# STM32L010F4P6.net
KiCad netlist of a schematic drawn in EAGLE
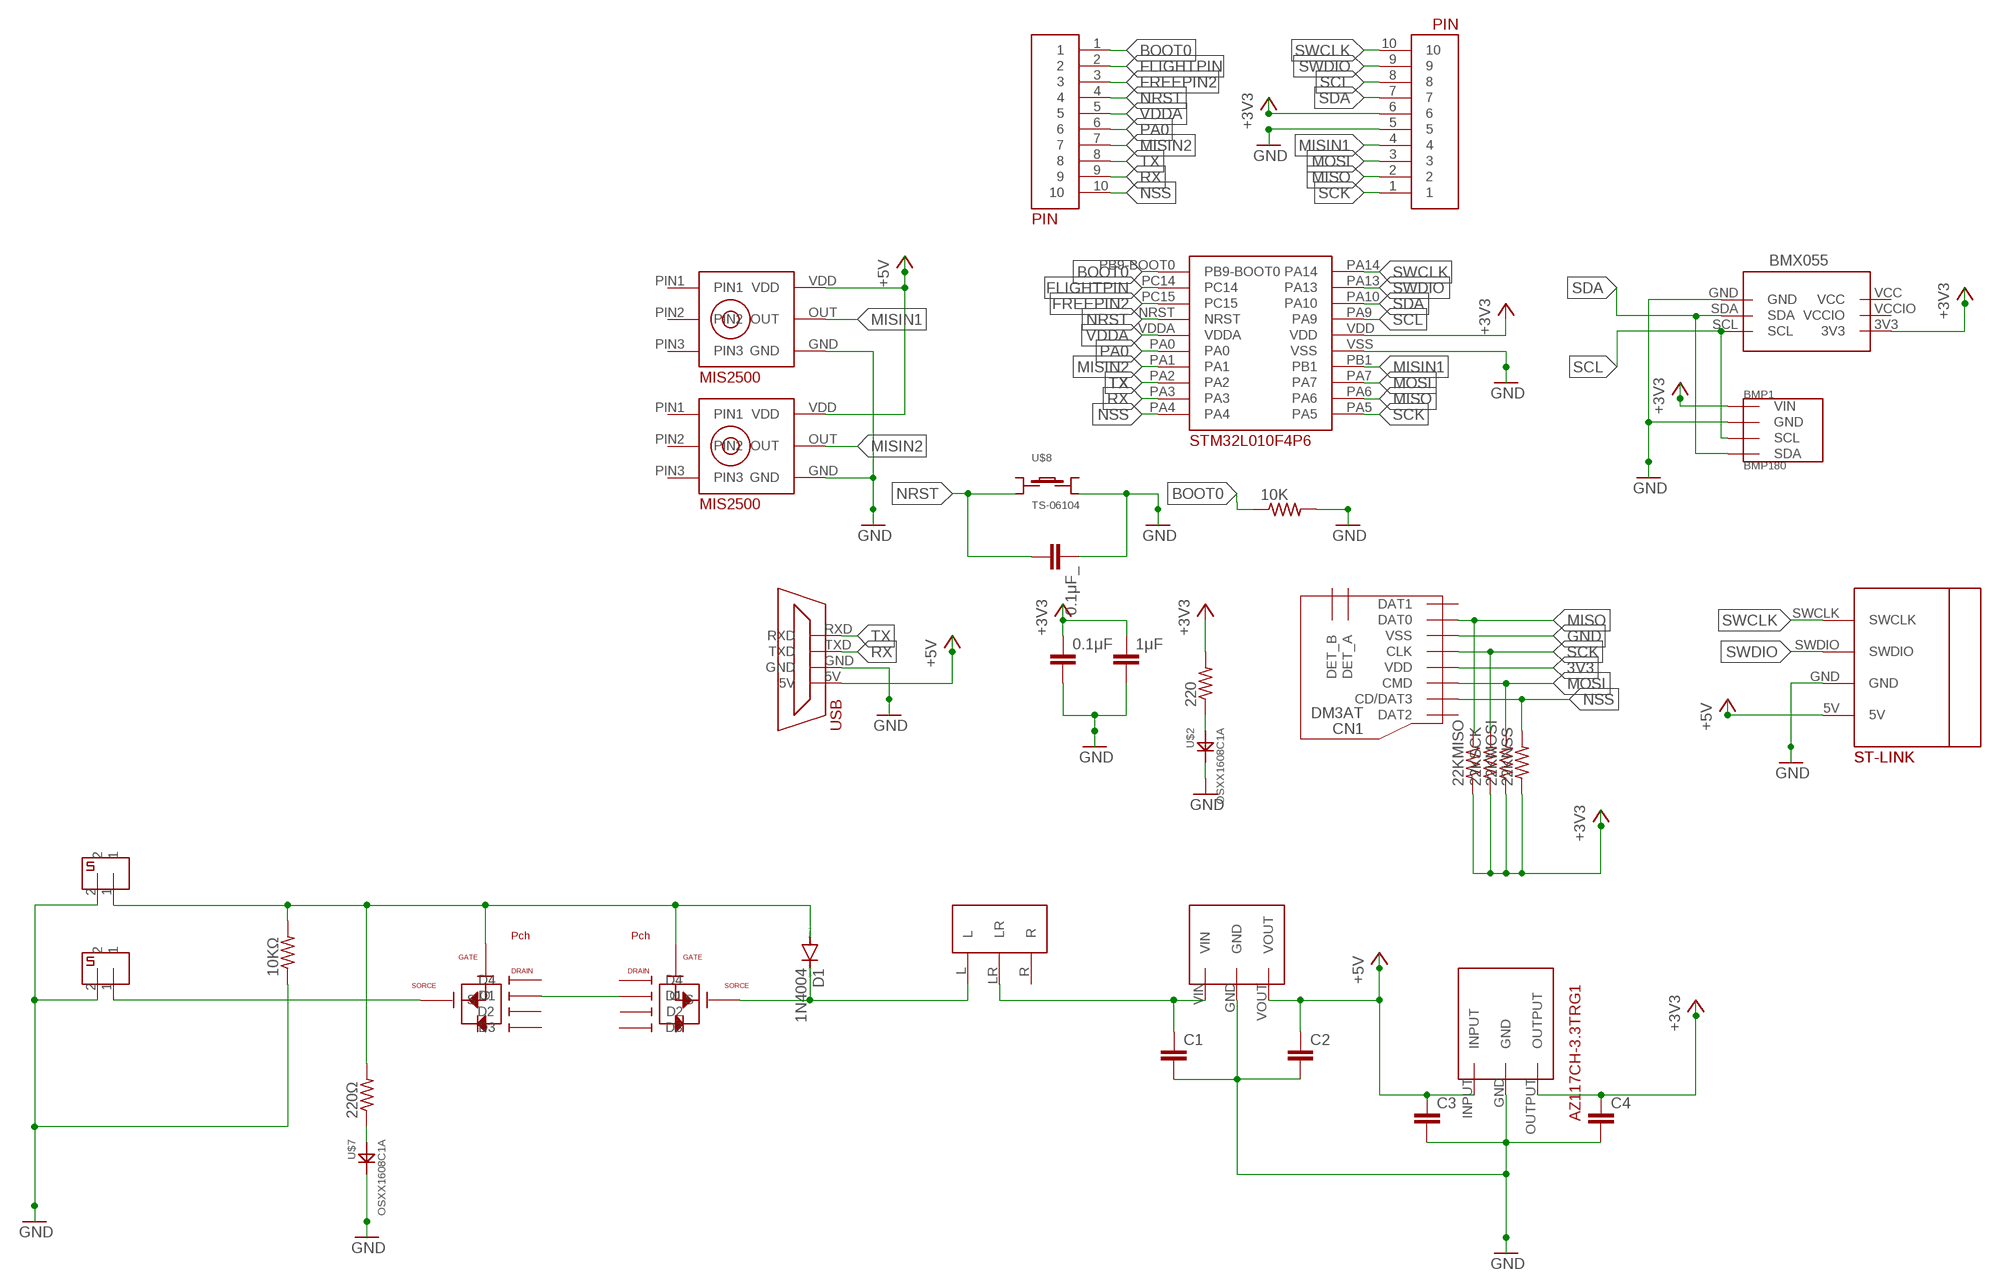
[diagram p0: schematic, sheet 1]

(export (version "E")
  (design (tool "Eeschema 10.0.6"))
  (components
    (comp (ref "0.1μF")
      (value "C-EUC0603")
      (footprint "eagle-import:C0603")
      (libsource (lib "eagle-import") (part "C-EUC0603"))
    )
    (comp (ref "0.1μF_")
      (value "C-EUC0603")
      (footprint "eagle-import:C0603")
      (libsource (lib "eagle-import") (part "C-EUC0603"))
    )
    (comp (ref "1μF")
      (value "C-EUC0805")
      (footprint "eagle-import:C0805")
      (libsource (lib "eagle-import") (part "C-EUC0805"))
    )
    (comp (ref "10K")
      (value "R-US_R0603")
      (footprint "eagle-import:R0603")
      (libsource (lib "eagle-import") (part "R-US_R0603"))
    )
    (comp (ref "10KΩ")
      (value "R-US_R0603")
      (footprint "eagle-import:R0603")
      (libsource (lib "eagle-import") (part "R-US_R0603"))
    )
    (comp (ref "22KMISO")
      (value "R-US_R0603")
      (footprint "eagle-import:R0603")
      (libsource (lib "eagle-import") (part "R-US_R0603"))
    )
    (comp (ref "22KMOSI")
      (value "R-US_R0603")
      (footprint "eagle-import:R0603")
      (libsource (lib "eagle-import") (part "R-US_R0603"))
    )
    (comp (ref "22KNSS")
      (value "R-US_R0603")
      (footprint "eagle-import:R0603")
      (libsource (lib "eagle-import") (part "R-US_R0603"))
    )
    (comp (ref "22KSCK")
      (value "R-US_R0603")
      (footprint "eagle-import:R0603")
      (libsource (lib "eagle-import") (part "R-US_R0603"))
    )
    (comp (ref "220")
      (value "R-US_R0603")
      (footprint "eagle-import:R0603")
      (libsource (lib "eagle-import") (part "R-US_R0603"))
    )
    (comp (ref "220Ω")
      (value "R-US_R0603")
      (footprint "eagle-import:R0603")
      (libsource (lib "eagle-import") (part "R-US_R0603"))
    )
    (comp (ref "BMP1")
      (value "BMP180")
      (footprint "eagle-import:GY-68")
      (libsource (lib "eagle-import") (part "BMP180"))
    )
    (comp (ref "BMX1")
      (value "BMX055")
      (footprint "eagle-import:BMX055")
      (libsource (lib "eagle-import") (part "BMX055"))
    )
    (comp (ref "C1")
      (value "C2,5-3")
      (footprint "eagle-import:C2.5-3")
      (libsource (lib "eagle-import") (part "C2,5-3"))
    )
    (comp (ref "C2")
      (value "C2,5-3")
      (footprint "eagle-import:C2.5-3")
      (libsource (lib "eagle-import") (part "C2,5-3"))
    )
    (comp (ref "C3")
      (value "C2,5-3")
      (footprint "eagle-import:C2.5-3")
      (libsource (lib "eagle-import") (part "C2,5-3"))
    )
    (comp (ref "C4")
      (value "C2,5-3")
      (footprint "eagle-import:C2.5-3")
      (libsource (lib "eagle-import") (part "C2,5-3"))
    )
    (comp (ref "CN1")
      (value "DM3AT")
      (footprint "eagle-import:DM3AT")
      (libsource (lib "eagle-import") (part "DM3AT"))
    )
    (comp (ref "CONNECTOR1")
      (value "2PIN")
      (footprint "eagle-import:2PIN")
      (libsource (lib "eagle-import") (part "2PIN"))
    )
    (comp (ref "CONNECTOR3")
      (value "2PIN")
      (footprint "eagle-import:2PIN")
      (libsource (lib "eagle-import") (part "2PIN"))
    )
    (comp (ref "D1")
      (value "1N4004")
      (footprint "eagle-import:DO41-10")
      (libsource (lib "eagle-import") (part "1N4004"))
    )
    (comp (ref "SRIDE_SWTCH1")
      (value "SRIDE_SWITCH")
      (footprint "eagle-import:SRIDE_SWITCH")
      (libsource (lib "eagle-import") (part "SRIDE_SWITCH"))
    )
    (comp (ref "U$1")
      (value "STM32L010F4P6")
      (footprint "eagle-import:STM32L010F4P6")
      (libsource (lib "eagle-import") (part "STM32L010F4P6"))
    )
    (comp (ref "U$2")
      (value "OSXX1608C1A")
      (footprint "eagle-import:OSXX1608C1A")
      (libsource (lib "eagle-import") (part "OSXX1608C1A"))
    )
    (comp (ref "U$3")
      (value "MIS2500")
      (footprint "eagle-import:MIS2500")
      (libsource (lib "eagle-import") (part "MIS2500"))
    )
    (comp (ref "U$4")
      (value "MIS2500")
      (footprint "eagle-import:MIS2500")
      (libsource (lib "eagle-import") (part "MIS2500"))
    )
    (comp (ref "U$5")
      (value "STLINK")
      (footprint "eagle-import:STLINK")
      (libsource (lib "eagle-import") (part "STLINK"))
    )
    (comp (ref "U$6")
      (value "SSM6J808R")
      (footprint "eagle-import:SSM6J808R")
      (libsource (lib "eagle-import") (part "SSM6J808R"))
    )
    (comp (ref "U$7")
      (value "OSXX1608C1A")
      (footprint "eagle-import:OSXX1608C1A")
      (libsource (lib "eagle-import") (part "OSXX1608C1A"))
    )
    (comp (ref "U$8")
      (value "TS-06104")
      (footprint "eagle-import:TS-06104")
      (libsource (lib "eagle-import") (part "TS-06104"))
    )
    (comp (ref "U$9")
      (value "SSM6J808R")
      (footprint "eagle-import:SSM6J808R")
      (libsource (lib "eagle-import") (part "SSM6J808R"))
    )
    (comp (ref "U$11")
      (value "M78AR05-1")
      (footprint "eagle-import:M78AR05-1")
      (libsource (lib "eagle-import") (part "M78AR05-1"))
    )
    (comp (ref "U$12")
      (value "10PIN")
      (footprint "eagle-import:10PIN")
      (libsource (lib "eagle-import") (part "10PIN"))
    )
    (comp (ref "U$13")
      (value "10PIN")
      (footprint "eagle-import:10PIN")
      (libsource (lib "eagle-import") (part "10PIN"))
    )
    (comp (ref "U$14")
      (value "F234X")
      (footprint "eagle-import:FT234X")
      (libsource (lib "eagle-import") (part "F234X"))
    )
    (comp (ref "U$17")
      (value "AZ117CH-3.3TRG1")
      (footprint "eagle-import:AZ117CH-3.3TRG1")
      (libsource (lib "eagle-import") (part "AZ117CH-3.3TRG1"))
    )
  )
  (nets
    (net (code "1") (name "+3V3") (class "Default")
      (node (ref "0.1μF") (pin "1") (pinfunction "1_1") (pintype "passive"))
      (node (ref "1μF") (pin "1") (pinfunction "1_1") (pintype "passive"))
      (node (ref "220") (pin "2") (pinfunction "2_2") (pintype "passive"))
      (node (ref "22KMISO") (pin "1") (pinfunction "1_1") (pintype "passive"))
      (node (ref "22KMOSI") (pin "1") (pinfunction "1_1") (pintype "passive"))
      (node (ref "22KNSS") (pin "1") (pinfunction "1_1") (pintype "passive"))
      (node (ref "22KSCK") (pin "1") (pinfunction "1_1") (pintype "passive"))
      (node (ref "BMP1") (pin "P1") (pinfunction "VIN_P1") (pintype "bidirectional"))
      (node (ref "BMX1") (pin "3V3") (pinfunction "3V3_3V3") (pintype "power_in"))
      (node (ref "C4") (pin "1") (pinfunction "1_1") (pintype "passive"))
      (node (ref "U$1") (pin "VDD") (pinfunction "VDD_VDD") (pintype "power_in"))
      (node (ref "U$13") (pin "6") (pinfunction "6_6") (pintype "bidirectional"))
      (node (ref "U$17") (pin "OUTPUT") (pinfunction "OUTPUT_OUTPUT") (pintype "bidirectional"))
    )
    (net (code "2") (name "+5V") (class "Default")
      (node (ref "C2") (pin "1") (pinfunction "1_1") (pintype "passive"))
      (node (ref "C3") (pin "1") (pinfunction "1_1") (pintype "passive"))
      (node (ref "U$11") (pin "VOUT") (pinfunction "VOUT_VOUT") (pintype "bidirectional"))
      (node (ref "U$14") (pin "5V") (pinfunction "5V_5V") (pintype "bidirectional"))
      (node (ref "U$17") (pin "INPUT") (pinfunction "INPUT_INPUT") (pintype "bidirectional"))
      (node (ref "U$3") (pin "VDD") (pinfunction "VDD_VDD") (pintype "bidirectional"))
      (node (ref "U$4") (pin "VDD") (pinfunction "VDD_VDD") (pintype "bidirectional"))
      (node (ref "U$5") (pin "5V") (pinfunction "5V_5V") (pintype "bidirectional"))
    )
    (net (code "3") (name "/VCC") (class "Default")
      (node (ref "BMX1") (pin "VCC") (pinfunction "VCC_VCC") (pintype "power_in"))
    )
    (net (code "4") (name "/VCCIO") (class "Default")
      (node (ref "BMX1") (pin "VCCIO") (pinfunction "VCCIO_VCCIO") (pintype "power_in"))
    )
    (net (code "5") (name "3V3") (class "Default")
      (node (ref "CN1") (pin "VDD") (pinfunction "VDD_VDD") (pintype "bidirectional"))
    )
    (net (code "6") (name "BOOT0") (class "Default")
      (node (ref "10K") (pin "1") (pinfunction "1_1") (pintype "passive"))
      (node (ref "U$1") (pin "PB9-BOOT0") (pinfunction "PB9-BOOT0_PB9-BOOT0") (pintype "bidirectional"))
      (node (ref "U$12") (pin "1") (pinfunction "1_1") (pintype "bidirectional"))
    )
    (net (code "7") (name "FLIGHTPIN") (class "Default")
      (node (ref "U$1") (pin "PC14") (pinfunction "PC14_PC14") (pintype "bidirectional"))
      (node (ref "U$12") (pin "2") (pinfunction "2_2") (pintype "bidirectional"))
    )
    (net (code "8") (name "FREEPIN2") (class "Default")
      (node (ref "U$1") (pin "PC15") (pinfunction "PC15_PC15") (pintype "bidirectional"))
      (node (ref "U$12") (pin "3") (pinfunction "3_3") (pintype "bidirectional"))
    )
    (net (code "9") (name "GND") (class "Default")
      (node (ref "0.1μF") (pin "2") (pinfunction "2_2") (pintype "passive"))
      (node (ref "0.1μF_") (pin "1") (pinfunction "1_1") (pintype "passive"))
      (node (ref "10K") (pin "2") (pinfunction "2_2") (pintype "passive"))
      (node (ref "10KΩ") (pin "1") (pinfunction "1_1") (pintype "passive"))
      (node (ref "1μF") (pin "2") (pinfunction "2_2") (pintype "passive"))
      (node (ref "BMP1") (pin "P2") (pinfunction "GND_P2") (pintype "bidirectional"))
      (node (ref "BMX1") (pin "GND") (pinfunction "GND_GND") (pintype "power_in"))
      (node (ref "C1") (pin "2") (pinfunction "2_2") (pintype "passive"))
      (node (ref "C2") (pin "2") (pinfunction "2_2") (pintype "passive"))
      (node (ref "C3") (pin "2") (pinfunction "2_2") (pintype "passive"))
      (node (ref "C4") (pin "2") (pinfunction "2_2") (pintype "passive"))
      (node (ref "CN1") (pin "VSS") (pinfunction "VSS_VSS") (pintype "bidirectional"))
      (node (ref "CONNECTOR1") (pin "2") (pinfunction "2_2") (pintype "bidirectional"))
      (node (ref "CONNECTOR3") (pin "2") (pinfunction "2_2") (pintype "bidirectional"))
      (node (ref "U$1") (pin "VSS") (pinfunction "VSS_VSS") (pintype "power_in"))
      (node (ref "U$11") (pin "GND") (pinfunction "GND_GND") (pintype "bidirectional"))
      (node (ref "U$13") (pin "5") (pinfunction "5_5") (pintype "bidirectional"))
      (node (ref "U$14") (pin "GND") (pinfunction "GND_GND") (pintype "bidirectional"))
      (node (ref "U$17") (pin "GND") (pinfunction "GND_GND") (pintype "bidirectional"))
      (node (ref "U$2") (pin "CT") (pinfunction "CT_CT") (pintype "bidirectional"))
      (node (ref "U$3") (pin "GND") (pinfunction "GND_GND") (pintype "bidirectional"))
      (node (ref "U$4") (pin "GND") (pinfunction "GND_GND") (pintype "bidirectional"))
      (node (ref "U$5") (pin "GND") (pinfunction "GND_GND") (pintype "bidirectional"))
      (node (ref "U$7") (pin "CT") (pinfunction "CT_CT") (pintype "bidirectional"))
      (node (ref "U$8") (pin "D") (pinfunction "D_D") (pintype "bidirectional"))
    )
    (net (code "10") (name "MISIN1") (class "Default")
      (node (ref "U$1") (pin "PB1") (pinfunction "PB1_PB1") (pintype "bidirectional"))
      (node (ref "U$13") (pin "4") (pinfunction "4_4") (pintype "bidirectional"))
      (node (ref "U$3") (pin "OUT") (pinfunction "OUT_OUT") (pintype "bidirectional"))
    )
    (net (code "11") (name "MISIN2") (class "Default")
      (node (ref "U$1") (pin "PA1") (pinfunction "PA1_PA1") (pintype "bidirectional"))
      (node (ref "U$12") (pin "7") (pinfunction "7_7") (pintype "bidirectional"))
      (node (ref "U$4") (pin "OUT") (pinfunction "OUT_OUT") (pintype "bidirectional"))
    )
    (net (code "12") (name "MISO") (class "Default")
      (node (ref "22KMISO") (pin "2") (pinfunction "2_2") (pintype "passive"))
      (node (ref "CN1") (pin "DAT0") (pinfunction "DAT0_DAT0") (pintype "bidirectional"))
      (node (ref "U$1") (pin "PA6") (pinfunction "PA6_PA6") (pintype "bidirectional"))
      (node (ref "U$13") (pin "2") (pinfunction "2_2") (pintype "bidirectional"))
    )
    (net (code "13") (name "MOSI") (class "Default")
      (node (ref "22KMOSI") (pin "2") (pinfunction "2_2") (pintype "passive"))
      (node (ref "CN1") (pin "CMD") (pinfunction "CMD_CMD") (pintype "bidirectional"))
      (node (ref "U$1") (pin "PA7") (pinfunction "PA7_PA7") (pintype "bidirectional"))
      (node (ref "U$13") (pin "3") (pinfunction "3_3") (pintype "bidirectional"))
    )
    (net (code "14") (name "NRST") (class "Default")
      (node (ref "0.1μF_") (pin "2") (pinfunction "2_2") (pintype "passive"))
      (node (ref "U$1") (pin "NRST") (pinfunction "NRST_NRST") (pintype "bidirectional"))
      (node (ref "U$12") (pin "4") (pinfunction "4_4") (pintype "bidirectional"))
      (node (ref "U$8") (pin "B") (pinfunction "B_B") (pintype "bidirectional"))
    )
    (net (code "15") (name "NSS") (class "Default")
      (node (ref "22KNSS") (pin "2") (pinfunction "2_2") (pintype "passive"))
      (node (ref "CN1") (pin "CD/DAT3") (pinfunction "CD/DAT3_CD/DAT3") (pintype "bidirectional"))
      (node (ref "U$1") (pin "PA4") (pinfunction "PA4_PA4") (pintype "bidirectional"))
      (node (ref "U$12") (pin "10") (pinfunction "10_10") (pintype "bidirectional"))
    )
    (net (code "16") (name "Net-(10KΩ-Pad2)") (class "Default")
      (node (ref "10KΩ") (pin "2") (pinfunction "2_2") (pintype "passive"))
      (node (ref "220Ω") (pin "2") (pinfunction "2_2") (pintype "passive"))
      (node (ref "CONNECTOR1") (pin "1") (pinfunction "1_1") (pintype "bidirectional"))
      (node (ref "D1") (pin "A") (pinfunction "A_A") (pintype "passive"))
      (node (ref "U$6") (pin "G") (pinfunction "G_G") (pintype "bidirectional"))
      (node (ref "U$9") (pin "G") (pinfunction "G_G") (pintype "bidirectional"))
    )
    (net (code "17") (name "Net-(220-Pad1)") (class "Default")
      (node (ref "220") (pin "1") (pinfunction "1_1") (pintype "passive"))
      (node (ref "U$2") (pin "AN") (pinfunction "AN_AN") (pintype "bidirectional"))
    )
    (net (code "18") (name "Net-(220Ω-Pad1)") (class "Default")
      (node (ref "220Ω") (pin "1") (pinfunction "1_1") (pintype "passive"))
      (node (ref "U$7") (pin "AN") (pinfunction "AN_AN") (pintype "bidirectional"))
    )
    (net (code "19") (name "Net-(C1-Pad1)") (class "Default")
      (node (ref "C1") (pin "1") (pinfunction "1_1") (pintype "passive"))
      (node (ref "SRIDE_SWTCH1") (pin "LR") (pinfunction "LR_LR") (pintype "bidirectional"))
      (node (ref "U$11") (pin "VIN") (pinfunction "VIN_VIN") (pintype "bidirectional"))
    )
    (net (code "20") (name "Net-(CONNECTOR3-Pad1)") (class "Default")
      (node (ref "CONNECTOR3") (pin "1") (pinfunction "1_1") (pintype "bidirectional"))
      (node (ref "U$6") (pin "S") (pinfunction "S_S") (pintype "bidirectional"))
    )
    (net (code "21") (name "Net-(D1-PadC)") (class "Default")
      (node (ref "D1") (pin "C") (pinfunction "C_C") (pintype "passive"))
      (node (ref "SRIDE_SWTCH1") (pin "L") (pinfunction "L_L") (pintype "bidirectional"))
      (node (ref "U$9") (pin "S") (pinfunction "S_S") (pintype "bidirectional"))
    )
    (net (code "22") (name "Net-(U$6-PadD1)") (class "Default")
      (node (ref "U$6") (pin "D1") (pinfunction "D1_D1") (pintype "bidirectional"))
      (node (ref "U$9") (pin "D1") (pinfunction "D1_D1") (pintype "bidirectional"))
    )
    (net (code "23") (name "PA0") (class "Default")
      (node (ref "U$1") (pin "PA0") (pinfunction "PA0_PA0") (pintype "bidirectional"))
      (node (ref "U$12") (pin "6") (pinfunction "6_6") (pintype "bidirectional"))
    )
    (net (code "24") (name "RX") (class "Default")
      (node (ref "U$1") (pin "PA3") (pinfunction "PA3_PA3") (pintype "bidirectional"))
      (node (ref "U$12") (pin "9") (pinfunction "9_9") (pintype "bidirectional"))
      (node (ref "U$14") (pin "TXD") (pinfunction "TXD_TXD") (pintype "bidirectional"))
    )
    (net (code "25") (name "SCK") (class "Default")
      (node (ref "22KSCK") (pin "2") (pinfunction "2_2") (pintype "passive"))
      (node (ref "CN1") (pin "CLK") (pinfunction "CLK_CLK") (pintype "bidirectional"))
      (node (ref "U$1") (pin "PA5") (pinfunction "PA5_PA5") (pintype "bidirectional"))
      (node (ref "U$13") (pin "1") (pinfunction "1_1") (pintype "bidirectional"))
    )
    (net (code "26") (name "SCL") (class "Default")
      (node (ref "BMP1") (pin "P3") (pinfunction "SCL_P3") (pintype "bidirectional"))
      (node (ref "BMX1") (pin "SCL") (pinfunction "SCL_SCL") (pintype "bidirectional"))
      (node (ref "U$1") (pin "PA9") (pinfunction "PA9_PA9") (pintype "bidirectional"))
      (node (ref "U$13") (pin "8") (pinfunction "8_8") (pintype "bidirectional"))
    )
    (net (code "27") (name "SDA") (class "Default")
      (node (ref "BMX1") (pin "SDA") (pinfunction "SDA_SDA") (pintype "bidirectional"))
      (node (ref "U$1") (pin "PA10") (pinfunction "PA10_PA10") (pintype "bidirectional"))
      (node (ref "U$13") (pin "7") (pinfunction "7_7") (pintype "bidirectional"))
    )
    (net (code "28") (name "SWCLK") (class "Default")
      (node (ref "U$1") (pin "PA14") (pinfunction "PA14_PA14") (pintype "bidirectional"))
      (node (ref "U$13") (pin "10") (pinfunction "10_10") (pintype "bidirectional"))
      (node (ref "U$5") (pin "SWCLK") (pinfunction "SWCLK_SWCLK") (pintype "bidirectional"))
    )
    (net (code "29") (name "SWDIO") (class "Default")
      (node (ref "U$1") (pin "PA13") (pinfunction "PA13_PA13") (pintype "bidirectional"))
      (node (ref "U$13") (pin "9") (pinfunction "9_9") (pintype "bidirectional"))
      (node (ref "U$5") (pin "SWDIO") (pinfunction "SWDIO_SWDIO") (pintype "bidirectional"))
    )
    (net (code "30") (name "TX") (class "Default")
      (node (ref "U$1") (pin "PA2") (pinfunction "PA2_PA2") (pintype "bidirectional"))
      (node (ref "U$12") (pin "8") (pinfunction "8_8") (pintype "bidirectional"))
      (node (ref "U$14") (pin "RXD") (pinfunction "RXD_RXD") (pintype "bidirectional"))
    )
    (net (code "31") (name "VDDA") (class "Default")
      (node (ref "U$1") (pin "VDDA") (pinfunction "VDDA_VDDA") (pintype "power_in"))
      (node (ref "U$12") (pin "5") (pinfunction "5_5") (pintype "bidirectional"))
    )
    (net (code "32") (name "unconnected-(BMP1-SDA-PadP4)") (class "Default")
      (node (ref "BMP1") (pin "P4") (pinfunction "SDA_P4") (pintype "bidirectional"))
    )
    (net (code "33") (name "unconnected-(CN1-PadDAT1)") (class "Default")
      (node (ref "CN1") (pin "DAT1") (pinfunction "DAT1_DAT1") (pintype "bidirectional"))
    )
    (net (code "34") (name "unconnected-(CN1-PadDAT2)") (class "Default")
      (node (ref "CN1") (pin "DAT2") (pinfunction "DAT2_DAT2") (pintype "bidirectional"))
    )
    (net (code "35") (name "unconnected-(CN1-PadDET_A)") (class "Default")
      (node (ref "CN1") (pin "DET_A") (pinfunction "DET_A_DET_A") (pintype "bidirectional"))
    )
    (net (code "36") (name "unconnected-(CN1-PadDET_B)") (class "Default")
      (node (ref "CN1") (pin "DET_B") (pinfunction "DET_B_DET_B") (pintype "bidirectional"))
    )
    (net (code "37") (name "unconnected-(SRIDE_SWTCH1-PadR)") (class "Default")
      (node (ref "SRIDE_SWTCH1") (pin "R") (pinfunction "R_R") (pintype "bidirectional"))
    )
    (net (code "38") (name "unconnected-(U$3-PadPIN1)") (class "Default")
      (node (ref "U$3") (pin "PIN1") (pinfunction "PIN1_PIN1") (pintype "bidirectional"))
    )
    (net (code "39") (name "unconnected-(U$3-PadPIN2)") (class "Default")
      (node (ref "U$3") (pin "PIN2") (pinfunction "PIN2_PIN2") (pintype "bidirectional"))
    )
    (net (code "40") (name "unconnected-(U$3-PadPIN3)") (class "Default")
      (node (ref "U$3") (pin "PIN3") (pinfunction "PIN3_PIN3") (pintype "bidirectional"))
    )
    (net (code "41") (name "unconnected-(U$4-PadPIN1)") (class "Default")
      (node (ref "U$4") (pin "PIN1") (pinfunction "PIN1_PIN1") (pintype "bidirectional"))
    )
    (net (code "42") (name "unconnected-(U$4-PadPIN2)") (class "Default")
      (node (ref "U$4") (pin "PIN2") (pinfunction "PIN2_PIN2") (pintype "bidirectional"))
    )
    (net (code "43") (name "unconnected-(U$4-PadPIN3)") (class "Default")
      (node (ref "U$4") (pin "PIN3") (pinfunction "PIN3_PIN3") (pintype "bidirectional"))
    )
    (net (code "44") (name "unconnected-(U$6-PadD2)") (class "Default")
      (node (ref "U$6") (pin "D2") (pinfunction "D2_D2") (pintype "bidirectional"))
    )
    (net (code "45") (name "unconnected-(U$6-PadD3)") (class "Default")
      (node (ref "U$6") (pin "D3") (pinfunction "D3_D3") (pintype "bidirectional"))
    )
    (net (code "46") (name "unconnected-(U$6-PadD4)") (class "Default")
      (node (ref "U$6") (pin "D4") (pinfunction "D4_D4") (pintype "bidirectional"))
    )
    (net (code "47") (name "unconnected-(U$8-PadA)") (class "Default")
      (node (ref "U$8") (pin "A") (pinfunction "A_A") (pintype "bidirectional"))
    )
    (net (code "48") (name "unconnected-(U$8-PadC)") (class "Default")
      (node (ref "U$8") (pin "C") (pinfunction "C_C") (pintype "bidirectional"))
    )
    (net (code "49") (name "unconnected-(U$9-PadD2)") (class "Default")
      (node (ref "U$9") (pin "D2") (pinfunction "D2_D2") (pintype "bidirectional"))
    )
    (net (code "50") (name "unconnected-(U$9-PadD3)") (class "Default")
      (node (ref "U$9") (pin "D3") (pinfunction "D3_D3") (pintype "bidirectional"))
    )
    (net (code "51") (name "unconnected-(U$9-PadD4)") (class "Default")
      (node (ref "U$9") (pin "D4") (pinfunction "D4_D4") (pintype "bidirectional"))
    )
  )
)
